# ultrasonic_tank_monitor_battery.net
KiCad netlist of a schematic drawn in Altium Designer
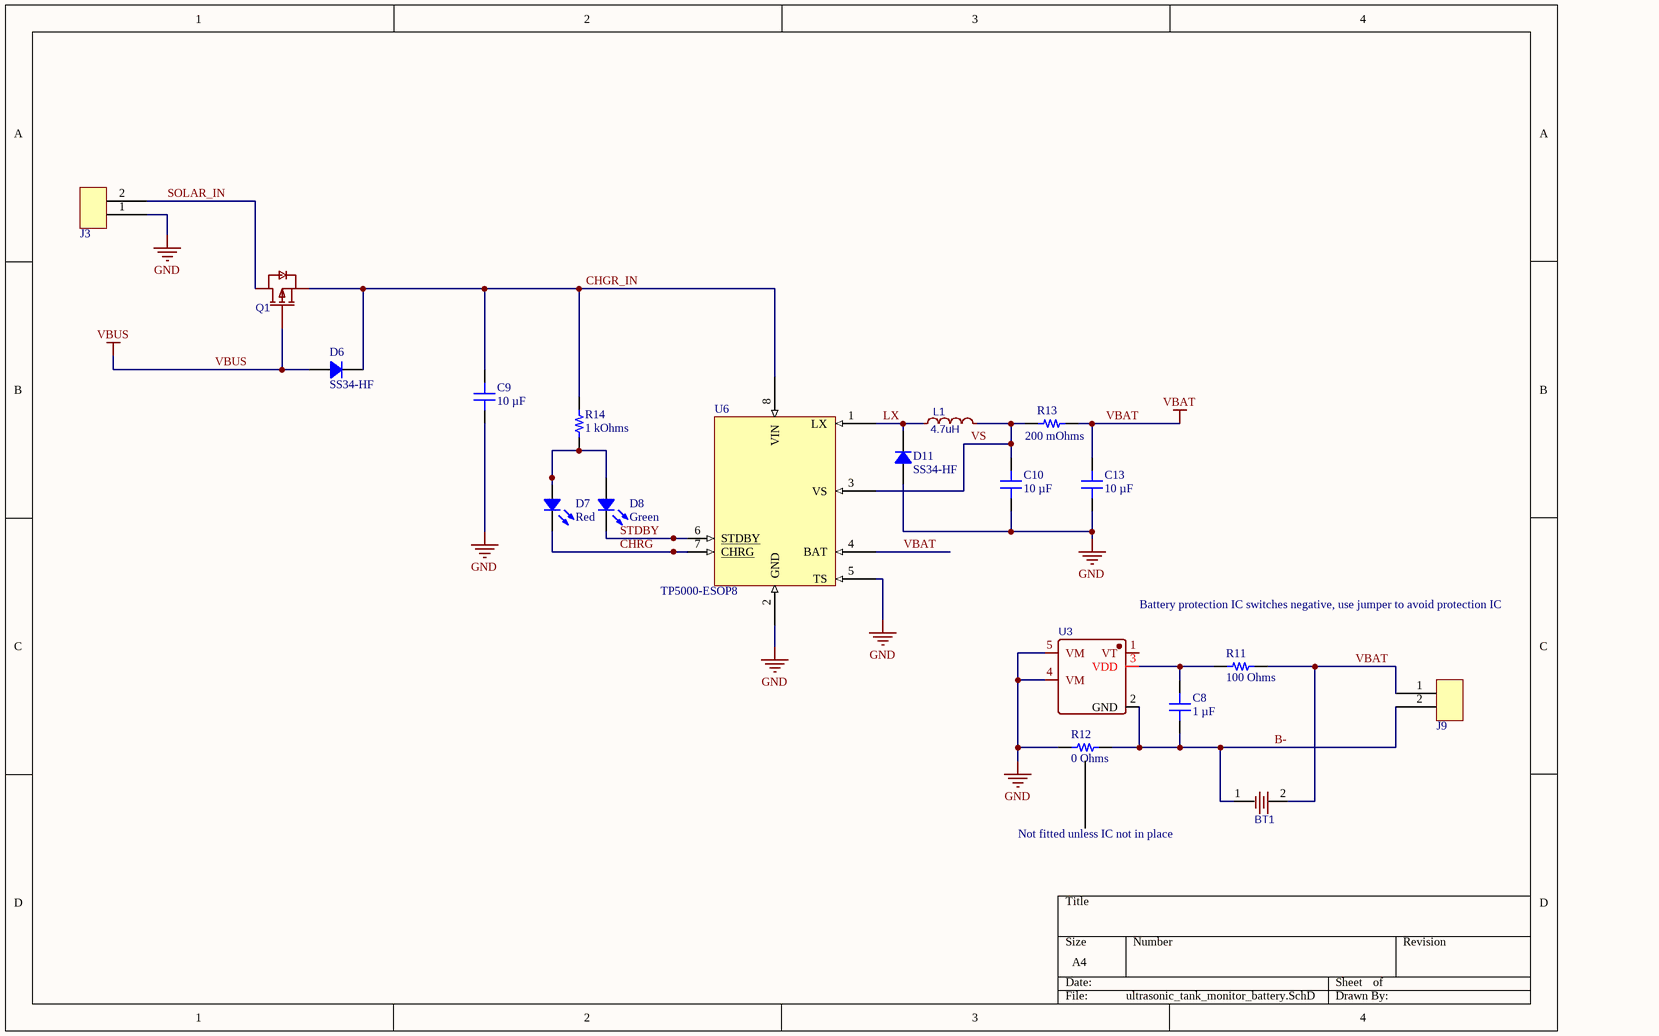
[diagram p0: ultrasonic_tank_monitor_battery.SchDoc]

(export (version "E")
  (design (tool "Eeschema 10.0.6"))
  (components
    (comp (ref "BT1")
      (value "BH-18650-B1BA002")
      (footprint "BATTERY-SMD_18650-1S-L77.1-W20.7-1")
      (description "18650 SMD battery holder")
      (fields (field (name "MANUFACTURER") "MYOUNG(美阳)") (field (name "CONTRIBUTOR") "lcsc"))
      (libsource (lib "Pidgeon_SCH") (part "18650 SMD battery holder"))
    )
    (comp (ref "C8")
      (value "1 µF")
      (footprint "CAP 0603_1608")
      (description "CAP CER 1UF 10V X7R 0603")
      (fields (field (name "PART NUMBER") "LMK107B7105KAHT") (field (name "MANUFACTURER") "Taiyo Yuden"))
      (libsource (lib "Celestial Altium Library - altium_library") (part "Capacitor"))
    )
    (comp (ref "C9")
      (value "10 µF")
      (footprint "CAP 0603_1608")
      (description "CAP CER 10UF 10V X5R 0603")
      (fields
        (field (name "PART NUMBER") "GRM188R61A106ME69D")
        (field (name "MANUFACTURER") "Murata Electronics")
      )
      (libsource (lib "Celestial Altium Library - altium_library") (part "Capacitor"))
    )
    (comp (ref "C10")
      (value "10 µF")
      (footprint "CAP 0603_1608")
      (description "CAP CER 10UF 10V X5R 0603")
      (fields
        (field (name "PART NUMBER") "GRM188R61A106ME69D")
        (field (name "MANUFACTURER") "Murata Electronics")
      )
      (libsource (lib "Celestial Altium Library - altium_library") (part "Capacitor"))
    )
    (comp (ref "C13")
      (value "10 µF")
      (footprint "CAP 0603_1608")
      (description "CAP CER 10UF 10V X5R 0603")
      (fields
        (field (name "PART NUMBER") "GRM188R61A106ME69D")
        (field (name "MANUFACTURER") "Murata Electronics")
      )
      (libsource (lib "Celestial Altium Library - altium_library") (part "Capacitor"))
    )
    (comp (ref "D6")
      (value "SS34-HF")
      (footprint "DO214AC SMA")
      (description "DIODE SCHOTTKY 40V 3A DO214AC")
      (fields (field (name "MANUFACTURER") "Comchip Technology"))
      (libsource (lib "Celestial Altium Library - altium_library") (part "Diode"))
    )
    (comp (ref "D7")
      (value "Red")
      (footprint "LED 0805_2012 RED")
      (description "LED RED 0805 SMD")
      (fields (field (name "PART NUMBER") "5990110007F") (field (name "MANUFACTURER") "Dialight"))
      (libsource (lib "Celestial Altium Library - altium_library") (part "LED"))
    )
    (comp (ref "D8")
      (value "Green")
      (footprint "LED 0805_2012 GREEN")
      (description "LED GREEN 0805 SMD")
      (fields (field (name "PART NUMBER") "5990181007F") (field (name "MANUFACTURER") "Dialight"))
      (libsource (lib "Celestial Altium Library - altium_library") (part "LED"))
    )
    (comp (ref "D11")
      (value "SS34-HF")
      (footprint "DO214AC SMA")
      (description "DIODE SCHOTTKY 40V 3A DO214AC")
      (fields (field (name "MANUFACTURER") "Comchip Technology"))
      (libsource (lib "Celestial Altium Library - altium_library") (part "Diode"))
    )
    (comp (ref "J3")
      (value "B2B-PH-K-S")
      (footprint "CONN-TH_B2B-PH-K-S")
      (description "2 Pin JST PH 2.0 Connector Straight")
      (libsource (lib "Pidgeon_SCH") (part "B2B-PH-K-S"))
    )
    (comp (ref "J9")
      (value "S2B-PH-K-S")
      (footprint "CONN-TH_S2B-PH-K-S-LF-SN")
      (description "2 Pin JST PH 2.0 Connector RA")
      (libsource (lib "Pidgeon_SCH") (part "S2B-PH-K-S"))
    )
    (comp (ref "L1")
      (value "4.7uH")
      (footprint "IND-SMD_L5.2-W5.2_YSPI0530")
      (description "2.2uH 1.5A Power Inductor 3x3")
      (fields
        (field (name "MANUFACTURER") "TAIYO YUDEN(太诱)")
        (field (name "MANUFACTURER PART") "NR3015T2R2M")
      )
      (libsource (lib "Pidgeon_SCH") (part "4.7uH 5.2x5.4 SMD 3.5A"))
    )
    (comp (ref "Q1")
      (value "SI2301-ZE")
      (footprint "SOT-23-3_L2.9-W1.3-P1.90-LS2.4-BR")
      (description "P-CHAN Mosfet SI2301")
      (fields (field (name "MANUFACTURER") "HXY MOSFET(华轩阳电子)") (field (name "CONTRIBUTOR") "lcsc"))
      (libsource (lib "Pidgeon_SCH") (part "SI2301-ZE"))
    )
    (comp (ref "R11")
      (value "100 Ohms")
      (footprint "RES 0603_1608")
      (description "RES 100 OHM 5% 1/10W 0603")
      (fields
        (field (name "PART NUMBER") "WR06X101 JTL")
        (field (name "MANUFACTURER") "Walsin Technology Corporation")
      )
      (libsource (lib "Celestial Altium Library - altium_library") (part "Resistor"))
    )
    (comp (ref "R12")
      (value "0 Ohms")
      (footprint "RES 1206_3216")
      (description "RES SMD 0 OHM 3/4W 1206 WIDE")
      (fields (field (name "PART NUMBER") "RCL06120000Z0EA") (field (name "MANUFACTURER") "Vishay Dale"))
      (libsource (lib "Celestial Altium Library - altium_library") (part "Resistor"))
    )
    (comp (ref "R13")
      (value "200 mOhms")
      (footprint "RES 1206_3216")
      (description "RES 0.2 OHM 1% 1/2W 1206")
      (fields (field (name "PART NUMBER") "PT1206FR-7W0R2L") (field (name "MANUFACTURER") "Yageo"))
      (libsource (lib "Celestial Altium Library - altium_library") (part "Resistor"))
    )
    (comp (ref "R14")
      (value "1 kOhms")
      (footprint "RES 0603_1608")
      (description "RES 1K OHM 5% 1/4W 0603")
      (fields (field (name "PART NUMBER") "SR0603JR-7T1KL") (field (name "MANUFACTURER") "Yageo"))
      (libsource (lib "Celestial Altium Library - altium_library") (part "Resistor"))
    )
    (comp (ref "U3")
      (value "SKCL3130ME")
      (footprint "SOT-23-5_L2.9-W1.6-P0.95-LS2.8-BR")
      (description "1 cell battery protection IC Li-ion OC OV UV SOT 23-5")
      (fields (field (name "MANUFACTURER") "SHIKUES(时科)") (field (name "CONTRIBUTOR") "LCSC"))
      (libsource (lib "Pidgeon_SCH") (part "SKCL3130ME"))
    )
    (comp (ref "U6")
      (value "TP5000-ESOP8")
      (footprint "ESOP-8_L4.9-W3.9-P1.27-LS6.0-BL-EP")
      (description "1 cell Li-ion / LIFEPO4 cell charger switchmode")
      (libsource (lib "Pidgeon_SCH") (part "TP5000-ESOP8"))
    )
  )
  (nets
    (net (code "1") (name "/B-") (class "Default")
      (node (ref "BT1") (pin "1") (pinfunction "1_1") (pintype "passive"))
      (node (ref "C8") (pin "2") (pinfunction "2_2") (pintype "passive"))
      (node (ref "J9") (pin "2") (pintype "power_in"))
      (node (ref "R12") (pin "2") (pinfunction "2_2") (pintype "passive"))
      (node (ref "U3") (pin "2") (pinfunction "GND_2") (pintype "passive"))
    )
    (net (code "2") (name "/CHGR_IN") (class "Default")
      (node (ref "C9") (pin "2") (pinfunction "2_2") (pintype "passive"))
      (node (ref "D6") (pin "2") (pinfunction "2_2") (pintype "passive"))
      (node (ref "Q1") (pin "2") (pinfunction "S_2") (pintype "passive"))
      (node (ref "R14") (pin "1") (pinfunction "1_1") (pintype "passive"))
      (node (ref "U6") (pin "8") (pinfunction "VIN_8") (pintype "input"))
    )
    (net (code "3") (name "/CHRG") (class "Default")
      (node (ref "D7") (pin "2") (pinfunction "2_2") (pintype "passive"))
      (node (ref "U6") (pin "7") (pinfunction "CHRG_7") (pintype "input"))
    )
    (net (code "4") (name "/LX") (class "Default")
      (node (ref "D11") (pin "2") (pinfunction "2_2") (pintype "passive"))
      (node (ref "L1") (pin "1") (pinfunction "1_1") (pintype "passive"))
      (node (ref "U6") (pin "1") (pinfunction "LX_1") (pintype "input"))
    )
    (net (code "5") (name "/SOLAR_IN") (class "Default")
      (node (ref "J3") (pin "2") (pintype "power_in"))
      (node (ref "Q1") (pin "3") (pinfunction "D_3") (pintype "passive"))
    )
    (net (code "6") (name "/STDBY") (class "Default")
      (node (ref "D8") (pin "2") (pinfunction "2_2") (pintype "passive"))
      (node (ref "U6") (pin "6") (pinfunction "STDBY_6") (pintype "input"))
    )
    (net (code "7") (name "/VS") (class "Default")
      (node (ref "C10") (pin "2") (pinfunction "2_2") (pintype "passive"))
      (node (ref "L1") (pin "2") (pinfunction "2_2") (pintype "passive"))
      (node (ref "R13") (pin "1") (pinfunction "1_1") (pintype "passive"))
      (node (ref "U6") (pin "3") (pinfunction "VS_3") (pintype "input"))
    )
    (net (code "8") (name "GND") (class "Default")
      (node (ref "C10") (pin "1") (pinfunction "1_1") (pintype "passive"))
      (node (ref "C13") (pin "1") (pinfunction "1_1") (pintype "passive"))
      (node (ref "C9") (pin "1") (pinfunction "1_1") (pintype "passive"))
      (node (ref "D11") (pin "1") (pinfunction "1_1") (pintype "passive"))
      (node (ref "J3") (pin "1") (pintype "power_in"))
      (node (ref "R12") (pin "1") (pinfunction "1_1") (pintype "passive"))
      (node (ref "U3") (pin "4") (pinfunction "VM_4") (pintype "passive"))
      (node (ref "U3") (pin "5") (pinfunction "VM_5") (pintype "passive"))
      (node (ref "U6") (pin "2") (pinfunction "GND_2") (pintype "input"))
      (node (ref "U6") (pin "5") (pinfunction "TS_5") (pintype "input"))
    )
    (net (code "9") (name "Net-(D7-Pad1)") (class "Default")
      (node (ref "D7") (pin "1") (pinfunction "1_1") (pintype "passive"))
      (node (ref "D8") (pin "1") (pinfunction "1_1") (pintype "passive"))
      (node (ref "R14") (pin "2") (pinfunction "2_2") (pintype "passive"))
    )
    (net (code "10") (name "Net-(U3-VDD)") (class "Default")
      (node (ref "C8") (pin "1") (pinfunction "1_1") (pintype "passive"))
      (node (ref "R11") (pin "1") (pinfunction "1_1") (pintype "passive"))
      (node (ref "U3") (pin "3") (pinfunction "VDD_3") (pintype "passive"))
    )
    (net (code "11") (name "VBAT") (class "Default")
      (node (ref "BT1") (pin "2") (pinfunction "2_2") (pintype "passive"))
      (node (ref "C13") (pin "2") (pinfunction "2_2") (pintype "passive"))
      (node (ref "J9") (pin "1") (pintype "power_in"))
      (node (ref "R11") (pin "2") (pinfunction "2_2") (pintype "passive"))
      (node (ref "R13") (pin "2") (pinfunction "2_2") (pintype "passive"))
      (node (ref "U6") (pin "4") (pinfunction "BAT_4") (pintype "input"))
    )
    (net (code "12") (name "VBUS") (class "Default")
      (node (ref "D6") (pin "1") (pinfunction "1_1") (pintype "passive"))
      (node (ref "Q1") (pin "1") (pinfunction "G_1") (pintype "passive"))
    )
    (net (code "13") (name "unconnected-(U3-VT-Pad1)") (class "Default")
      (node (ref "U3") (pin "1") (pinfunction "VT_1") (pintype "passive"))
    )
  )
)
